# 03_DUT_ICs.net
KiCad netlist of a schematic drawn in Altium Designer
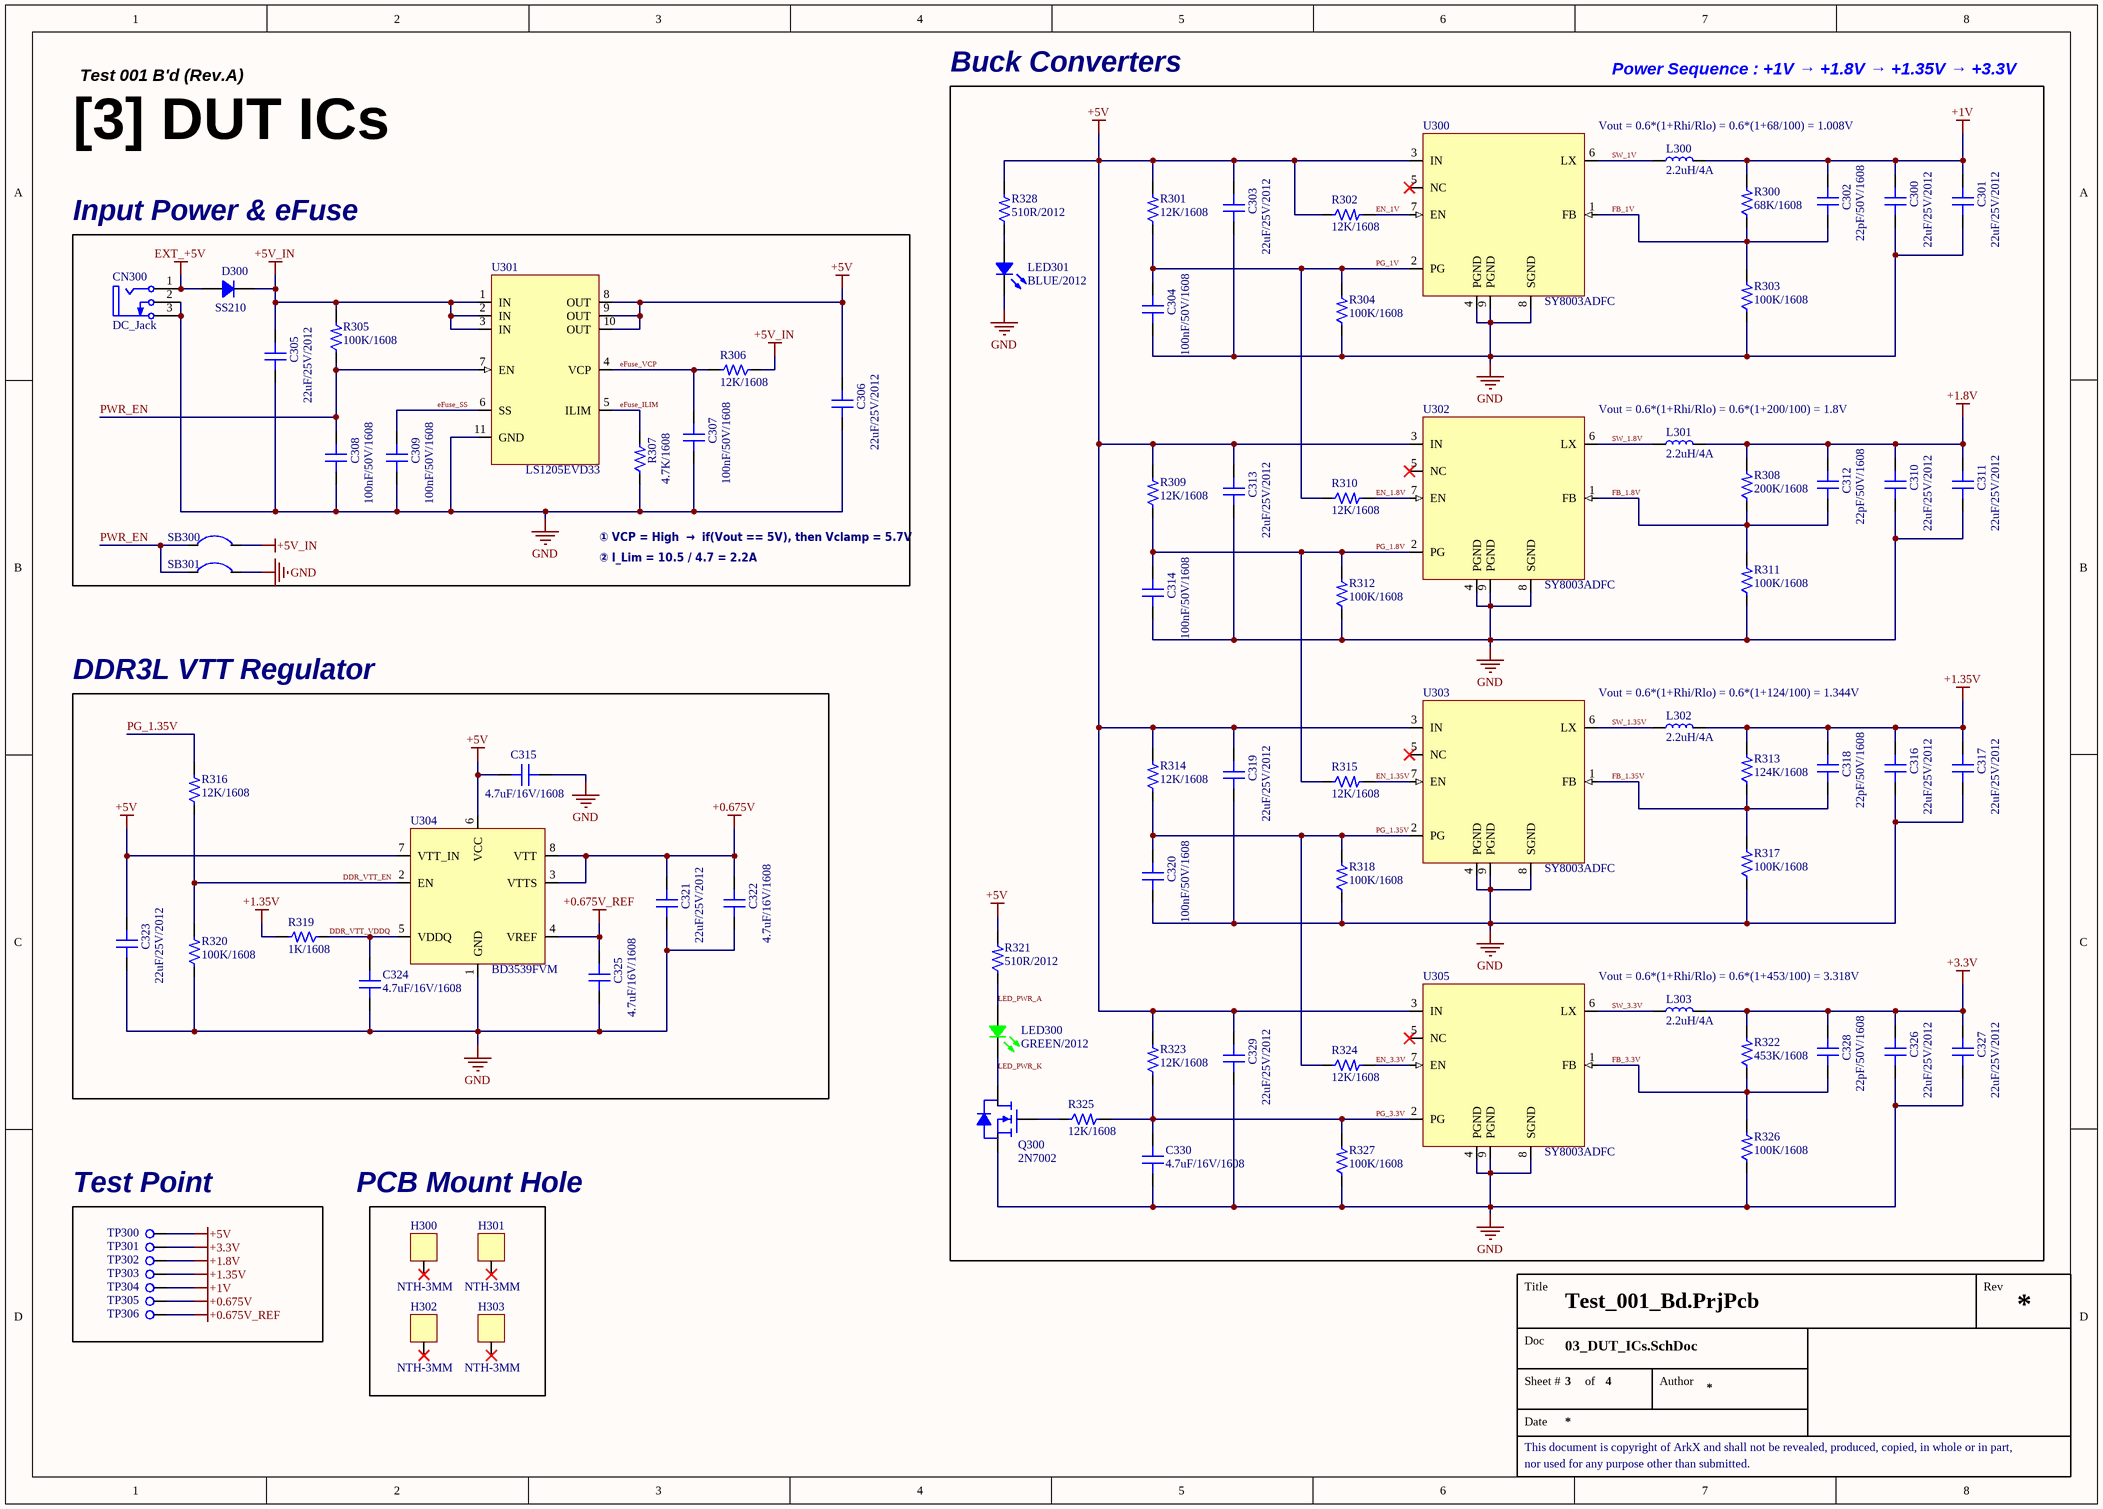
[diagram p0: 03_DUT_ICs.SchDoc]

(export (version "E")
  (design (tool "Eeschema 10.0.6"))
  (components
    (comp (ref "C300")
      (value "22uF/25V/2012")
      (footprint "CAP 2012 (0805_INCH)")
      (description "Ceramic CAP_22uF/25V/2012")
      (fields (field (name "LCSC PART #") "C45783"))
      (libsource (lib "Arkx") (part "CAP_22uF/25V/2012"))
    )
    (comp (ref "C301")
      (value "22uF/25V/2012")
      (footprint "CAP 2012 (0805_INCH)")
      (description "Ceramic CAP_22uF/25V/2012")
      (fields (field (name "LCSC PART #") "C45783"))
      (libsource (lib "Arkx") (part "CAP_22uF/25V/2012"))
    )
    (comp (ref "C302")
      (value "22pF/50V/1608")
      (footprint "CAP 1608 (0603_INCH)")
      (description "Ceramic CAP_22pF/50V/1608")
      (fields (field (name "LCSC PART #") "C1653"))
      (libsource (lib "Arkx") (part "CAP_22pF/50V/1608"))
    )
    (comp (ref "C303")
      (value "22uF/25V/2012")
      (footprint "CAP 2012 (0805_INCH)")
      (description "Ceramic CAP_22uF/25V/2012")
      (fields (field (name "LCSC PART #") "C45783"))
      (libsource (lib "Arkx") (part "CAP_22uF/25V/2012"))
    )
    (comp (ref "C304")
      (value "100nF/50V/1608")
      (footprint "CAP 1608 (0603_INCH)")
      (description "Ceramic CAP_100nF/50V/1608")
      (fields (field (name "LCSC PART #") "C14663"))
      (libsource (lib "Arkx") (part "CAP_100nF/50V/1608"))
    )
    (comp (ref "C305")
      (value "22uF/25V/2012")
      (footprint "CAP 2012 (0805_INCH)")
      (description "Ceramic CAP_22uF/25V/2012")
      (fields (field (name "LCSC PART #") "C45783"))
      (libsource (lib "Arkx") (part "CAP_22uF/25V/2012"))
    )
    (comp (ref "C306")
      (value "22uF/25V/2012")
      (footprint "CAP 2012 (0805_INCH)")
      (description "Ceramic CAP_22uF/25V/2012")
      (fields (field (name "LCSC PART #") "C45783"))
      (libsource (lib "Arkx") (part "CAP_22uF/25V/2012"))
    )
    (comp (ref "C307")
      (value "100nF/50V/1608")
      (footprint "CAP 1608 (0603_INCH)")
      (description "Ceramic CAP_100nF/50V/1608")
      (fields (field (name "LCSC PART #") "C14663"))
      (libsource (lib "Arkx") (part "CAP_100nF/50V/1608"))
    )
    (comp (ref "C308")
      (value "100nF/50V/1608")
      (footprint "CAP 1608 (0603_INCH)")
      (description "Ceramic CAP_100nF/50V/1608")
      (fields (field (name "LCSC PART #") "C14663"))
      (libsource (lib "Arkx") (part "CAP_100nF/50V/1608"))
    )
    (comp (ref "C309")
      (value "100nF/50V/1608")
      (footprint "CAP 1608 (0603_INCH)")
      (description "Ceramic CAP_100nF/50V/1608")
      (fields (field (name "LCSC PART #") "C14663"))
      (libsource (lib "Arkx") (part "CAP_100nF/50V/1608"))
    )
    (comp (ref "C310")
      (value "22uF/25V/2012")
      (footprint "CAP 2012 (0805_INCH)")
      (description "Ceramic CAP_22uF/25V/2012")
      (fields (field (name "LCSC PART #") "C45783"))
      (libsource (lib "Arkx") (part "CAP_22uF/25V/2012"))
    )
    (comp (ref "C311")
      (value "22uF/25V/2012")
      (footprint "CAP 2012 (0805_INCH)")
      (description "Ceramic CAP_22uF/25V/2012")
      (fields (field (name "LCSC PART #") "C45783"))
      (libsource (lib "Arkx") (part "CAP_22uF/25V/2012"))
    )
    (comp (ref "C312")
      (value "22pF/50V/1608")
      (footprint "CAP 1608 (0603_INCH)")
      (description "Ceramic CAP_22pF/50V/1608")
      (fields (field (name "LCSC PART #") "C1653"))
      (libsource (lib "Arkx") (part "CAP_22pF/50V/1608"))
    )
    (comp (ref "C313")
      (value "22uF/25V/2012")
      (footprint "CAP 2012 (0805_INCH)")
      (description "Ceramic CAP_22uF/25V/2012")
      (fields (field (name "LCSC PART #") "C45783"))
      (libsource (lib "Arkx") (part "CAP_22uF/25V/2012"))
    )
    (comp (ref "C314")
      (value "100nF/50V/1608")
      (footprint "CAP 1608 (0603_INCH)")
      (description "Ceramic CAP_100nF/50V/1608")
      (fields (field (name "LCSC PART #") "C14663"))
      (libsource (lib "Arkx") (part "CAP_100nF/50V/1608"))
    )
    (comp (ref "C315")
      (value "4.7uF/16V/1608")
      (footprint "CAP 1608 (0603_INCH)")
      (description "Ceramic CAP_4.7uF/16V/1608")
      (fields (field (name "LCSC PART #") "C19666"))
      (libsource (lib "Arkx") (part "CAP_4.7uF/16V/1608"))
    )
    (comp (ref "C316")
      (value "22uF/25V/2012")
      (footprint "CAP 2012 (0805_INCH)")
      (description "Ceramic CAP_22uF/25V/2012")
      (fields (field (name "LCSC PART #") "C45783"))
      (libsource (lib "Arkx") (part "CAP_22uF/25V/2012"))
    )
    (comp (ref "C317")
      (value "22uF/25V/2012")
      (footprint "CAP 2012 (0805_INCH)")
      (description "Ceramic CAP_22uF/25V/2012")
      (fields (field (name "LCSC PART #") "C45783"))
      (libsource (lib "Arkx") (part "CAP_22uF/25V/2012"))
    )
    (comp (ref "C318")
      (value "22pF/50V/1608")
      (footprint "CAP 1608 (0603_INCH)")
      (description "Ceramic CAP_22pF/50V/1608")
      (fields (field (name "LCSC PART #") "C1653"))
      (libsource (lib "Arkx") (part "CAP_22pF/50V/1608"))
    )
    (comp (ref "C319")
      (value "22uF/25V/2012")
      (footprint "CAP 2012 (0805_INCH)")
      (description "Ceramic CAP_22uF/25V/2012")
      (fields (field (name "LCSC PART #") "C45783"))
      (libsource (lib "Arkx") (part "CAP_22uF/25V/2012"))
    )
    (comp (ref "C320")
      (value "100nF/50V/1608")
      (footprint "CAP 1608 (0603_INCH)")
      (description "Ceramic CAP_100nF/50V/1608")
      (fields (field (name "LCSC PART #") "C14663"))
      (libsource (lib "Arkx") (part "CAP_100nF/50V/1608"))
    )
    (comp (ref "C321")
      (value "22uF/25V/2012")
      (footprint "CAP 2012 (0805_INCH)")
      (description "Ceramic CAP_22uF/25V/2012")
      (fields (field (name "LCSC PART #") "C45783"))
      (libsource (lib "Arkx") (part "CAP_22uF/25V/2012"))
    )
    (comp (ref "C322")
      (value "4.7uF/16V/1608")
      (footprint "CAP 1608 (0603_INCH)")
      (description "Ceramic CAP_4.7uF/16V/1608")
      (fields (field (name "LCSC PART #") "C19666"))
      (libsource (lib "Arkx") (part "CAP_4.7uF/16V/1608"))
    )
    (comp (ref "C323")
      (value "22uF/25V/2012")
      (footprint "CAP 2012 (0805_INCH)")
      (description "Ceramic CAP_22uF/25V/2012")
      (fields (field (name "LCSC PART #") "C45783"))
      (libsource (lib "Arkx") (part "CAP_22uF/25V/2012"))
    )
    (comp (ref "C324")
      (value "4.7uF/16V/1608")
      (footprint "CAP 1608 (0603_INCH)")
      (description "Ceramic CAP_4.7uF/16V/1608")
      (fields (field (name "LCSC PART #") "C19666"))
      (libsource (lib "Arkx") (part "CAP_4.7uF/16V/1608"))
    )
    (comp (ref "C325")
      (value "4.7uF/16V/1608")
      (footprint "CAP 1608 (0603_INCH)")
      (description "Ceramic CAP_4.7uF/16V/1608")
      (fields (field (name "LCSC PART #") "C19666"))
      (libsource (lib "Arkx") (part "CAP_4.7uF/16V/1608"))
    )
    (comp (ref "C326")
      (value "22uF/25V/2012")
      (footprint "CAP 2012 (0805_INCH)")
      (description "Ceramic CAP_22uF/25V/2012")
      (fields (field (name "LCSC PART #") "C45783"))
      (libsource (lib "Arkx") (part "CAP_22uF/25V/2012"))
    )
    (comp (ref "C327")
      (value "22uF/25V/2012")
      (footprint "CAP 2012 (0805_INCH)")
      (description "Ceramic CAP_22uF/25V/2012")
      (fields (field (name "LCSC PART #") "C45783"))
      (libsource (lib "Arkx") (part "CAP_22uF/25V/2012"))
    )
    (comp (ref "C328")
      (value "22pF/50V/1608")
      (footprint "CAP 1608 (0603_INCH)")
      (description "Ceramic CAP_22pF/50V/1608")
      (fields (field (name "LCSC PART #") "C1653"))
      (libsource (lib "Arkx") (part "CAP_22pF/50V/1608"))
    )
    (comp (ref "C329")
      (value "22uF/25V/2012")
      (footprint "CAP 2012 (0805_INCH)")
      (description "Ceramic CAP_22uF/25V/2012")
      (fields (field (name "LCSC PART #") "C45783"))
      (libsource (lib "Arkx") (part "CAP_22uF/25V/2012"))
    )
    (comp (ref "C330")
      (value "4.7uF/16V/1608")
      (footprint "CAP 1608 (0603_INCH)")
      (description "Ceramic CAP_4.7uF/16V/1608")
      (fields (field (name "LCSC PART #") "C19666"))
      (libsource (lib "Arkx") (part "CAP_4.7uF/16V/1608"))
    )
    (comp (ref "CN300")
      (value "DC_Jack")
      (footprint "CON DC-Jack")
      (libsource (lib "Arkx") (part "CON_DC-Jack"))
    )
    (comp (ref "D300")
      (value "SS210")
      (footprint "DIO DO-214AC (SMA)")
      (description "100V 850mV@2A 2A SMA(DO-214AC)  Schottky Barrier Diodes (SBD) ROHS")
      (fields (field (name "LCSC PART #") "C14996"))
      (libsource (lib "Arkx") (part "DIO_SS210"))
    )
    (comp (ref "H300")
      (value "NTH-3MM")
      (footprint "HOLE NTH-3MM")
      (description "Non-Through Hole 3mm")
      (libsource (lib "Arkx") (part "HOLE_NTH-3MM"))
    )
    (comp (ref "H301")
      (value "NTH-3MM")
      (footprint "HOLE NTH-3MM")
      (description "Non-Through Hole 3mm")
      (libsource (lib "Arkx") (part "HOLE_NTH-3MM"))
    )
    (comp (ref "H302")
      (value "NTH-3MM")
      (footprint "HOLE NTH-3MM")
      (description "Non-Through Hole 3mm")
      (libsource (lib "Arkx") (part "HOLE_NTH-3MM"))
    )
    (comp (ref "H303")
      (value "NTH-3MM")
      (footprint "HOLE NTH-3MM")
      (description "Non-Through Hole 3mm")
      (libsource (lib "Arkx") (part "HOLE_NTH-3MM"))
    )
    (comp (ref "L300")
      (value "2.2uH/4A")
      (footprint "IND BWVS006060282R2M00")
      (description "FIXED IND 2.2uH 4A 20mohm SMD")
      (libsource (lib "Arkx") (part "IND_BWVS006060282R2M00"))
    )
    (comp (ref "L301")
      (value "2.2uH/4A")
      (footprint "IND BWVS006060282R2M00")
      (description "FIXED IND 2.2uH 4A 20mohm SMD")
      (libsource (lib "Arkx") (part "IND_BWVS006060282R2M00"))
    )
    (comp (ref "L302")
      (value "2.2uH/4A")
      (footprint "IND BWVS006060282R2M00")
      (description "FIXED IND 2.2uH 4A 20mohm SMD")
      (libsource (lib "Arkx") (part "IND_BWVS006060282R2M00"))
    )
    (comp (ref "L303")
      (value "2.2uH/4A")
      (footprint "IND BWVS006060282R2M00")
      (description "FIXED IND 2.2uH 4A 20mohm SMD")
      (libsource (lib "Arkx") (part "IND_BWVS006060282R2M00"))
    )
    (comp (ref "LED300")
      (value "GREEN/2012")
      (footprint "LED MHT170RGBCT (GREEN)")
      (fields (field (name "LCSC PART #") "C2962094"))
      (libsource (lib "Arkx") (part "LED_MHT170RGBCT(GREEN)"))
    )
    (comp (ref "LED301")
      (value "BLUE/2012")
      (footprint "LED MHT170RGBCT (BLUE)")
      (fields (field (name "LCSC PART #") "C2962094"))
      (libsource (lib "Arkx") (part "LED_MHT170RGBCT(BLUE)"))
    )
    (comp (ref "Q300")
      (value "2N7002")
      (footprint "SOT 23-3 (DIODES INCORPORATED)")
      (description "60V 115mA 200mW 7.5Ω@10V,500mA N Channel SOT-23  MOSFETs ROHS")
      (fields (field (name "LCSC PART #") "C8545"))
      (libsource (lib "Arkx") (part "FET_2N7002"))
    )
    (comp (ref "R300")
      (value "68K/1608")
      (footprint "RES 1608 (0603_inch)")
      (description "RES_68K/1608/0.1W")
      (fields (field (name "LCSC PART #") "C23231"))
      (libsource (lib "Arkx") (part "RES_68K/1608/0.1W"))
    )
    (comp (ref "R301")
      (value "12K/1608")
      (footprint "RES 1608 (0603_inch)")
      (description "RES_12K/1608/0.1W")
      (fields (field (name "LCSC PART #") "C22790"))
      (libsource (lib "Arkx") (part "RES_12K/1608/0.1W"))
    )
    (comp (ref "R302")
      (value "12K/1608")
      (footprint "RES 1608 (0603_inch)")
      (description "RES_12K/1608/0.1W")
      (fields (field (name "LCSC PART #") "C22790"))
      (libsource (lib "Arkx") (part "RES_12K/1608/0.1W"))
    )
    (comp (ref "R303")
      (value "100K/1608")
      (footprint "RES 1608 (0603_inch)")
      (description "RES_100K/1608/0.1W")
      (fields (field (name "LCSC PART #") "C25803"))
      (libsource (lib "Arkx") (part "RES_100K/1608/0.1W"))
    )
    (comp (ref "R304")
      (value "100K/1608")
      (footprint "RES 1608 (0603_inch)")
      (description "RES_100K/1608/0.1W")
      (fields (field (name "LCSC PART #") "C25803"))
      (libsource (lib "Arkx") (part "RES_100K/1608/0.1W"))
    )
    (comp (ref "R305")
      (value "100K/1608")
      (footprint "RES 1608 (0603_inch)")
      (description "RES_100K/1608/0.1W")
      (fields (field (name "LCSC PART #") "C25803"))
      (libsource (lib "Arkx") (part "RES_100K/1608/0.1W"))
    )
    (comp (ref "R306")
      (value "12K/1608")
      (footprint "RES 1608 (0603_inch)")
      (description "RES_12K/1608/0.1W")
      (fields (field (name "LCSC PART #") "C22790"))
      (libsource (lib "Arkx") (part "RES_12K/1608/0.1W"))
    )
    (comp (ref "R307")
      (value "4.7K/1608")
      (footprint "RES 1608 (0603_inch)")
      (description "RES_4.7K/1608/0.1W")
      (fields (field (name "LCSC PART #") "C23162"))
      (libsource (lib "Arkx") (part "RES_4.7K/1608/0.1W"))
    )
    (comp (ref "R308")
      (value "200K/1608")
      (footprint "RES 1608 (0603_inch)")
      (description "RES_200K/1608/0.1W")
      (fields (field (name "LCSC PART #") "C25811"))
      (libsource (lib "Arkx") (part "RES_200K/1608/0.1W"))
    )
    (comp (ref "R309")
      (value "12K/1608")
      (footprint "RES 1608 (0603_inch)")
      (description "RES_12K/1608/0.1W")
      (fields (field (name "LCSC PART #") "C22790"))
      (libsource (lib "Arkx") (part "RES_12K/1608/0.1W"))
    )
    (comp (ref "R310")
      (value "12K/1608")
      (footprint "RES 1608 (0603_inch)")
      (description "RES_12K/1608/0.1W")
      (fields (field (name "LCSC PART #") "C22790"))
      (libsource (lib "Arkx") (part "RES_12K/1608/0.1W"))
    )
    (comp (ref "R311")
      (value "100K/1608")
      (footprint "RES 1608 (0603_inch)")
      (description "RES_100K/1608/0.1W")
      (fields (field (name "LCSC PART #") "C25803"))
      (libsource (lib "Arkx") (part "RES_100K/1608/0.1W"))
    )
    (comp (ref "R312")
      (value "100K/1608")
      (footprint "RES 1608 (0603_inch)")
      (description "RES_100K/1608/0.1W")
      (fields (field (name "LCSC PART #") "C25803"))
      (libsource (lib "Arkx") (part "RES_100K/1608/0.1W"))
    )
    (comp (ref "R313")
      (value "124K/1608")
      (footprint "RES 1608 (0603_inch)")
      (description "RES_124K/1608/0.1W")
      (fields (field (name "LCSC PART #") "C140118"))
      (libsource (lib "Arkx") (part "RES_124K/1608/0.1W"))
    )
    (comp (ref "R314")
      (value "12K/1608")
      (footprint "RES 1608 (0603_inch)")
      (description "RES_12K/1608/0.1W")
      (fields (field (name "LCSC PART #") "C22790"))
      (libsource (lib "Arkx") (part "RES_12K/1608/0.1W"))
    )
    (comp (ref "R315")
      (value "12K/1608")
      (footprint "RES 1608 (0603_inch)")
      (description "RES_12K/1608/0.1W")
      (fields (field (name "LCSC PART #") "C22790"))
      (libsource (lib "Arkx") (part "RES_12K/1608/0.1W"))
    )
    (comp (ref "R316")
      (value "12K/1608")
      (footprint "RES 1608 (0603_inch)")
      (description "RES_12K/1608/0.1W")
      (fields (field (name "LCSC PART #") "C22790"))
      (libsource (lib "Arkx") (part "RES_12K/1608/0.1W"))
    )
    (comp (ref "R317")
      (value "100K/1608")
      (footprint "RES 1608 (0603_inch)")
      (description "RES_100K/1608/0.1W")
      (fields (field (name "LCSC PART #") "C25803"))
      (libsource (lib "Arkx") (part "RES_100K/1608/0.1W"))
    )
    (comp (ref "R318")
      (value "100K/1608")
      (footprint "RES 1608 (0603_inch)")
      (description "RES_100K/1608/0.1W")
      (fields (field (name "LCSC PART #") "C25803"))
      (libsource (lib "Arkx") (part "RES_100K/1608/0.1W"))
    )
    (comp (ref "R319")
      (value "1K/1608")
      (footprint "RES 1608 (0603_inch)")
      (description "RES_1K/1608/0.1W")
      (fields (field (name "LCSC PART #") "C21190"))
      (libsource (lib "Arkx") (part "RES_1K/1608/0.1W"))
    )
    (comp (ref "R320")
      (value "100K/1608")
      (footprint "RES 1608 (0603_inch)")
      (description "RES_100K/1608/0.1W")
      (fields (field (name "LCSC PART #") "C25803"))
      (libsource (lib "Arkx") (part "RES_100K/1608/0.1W"))
    )
    (comp (ref "R321")
      (value "510R/2012")
      (footprint "RES 2012 (0805_inch)")
      (description "RES_510R/2012/0.125W")
      (fields (field (name "LCSC PART #") "C17734"))
      (libsource (lib "Arkx") (part "RES_510R/2012/0.125W"))
    )
    (comp (ref "R322")
      (value "453K/1608")
      (footprint "RES 1608 (0603_inch)")
      (description "RES_453K/1608/0.1W")
      (fields (field (name "LCSC PART #") "C25818"))
      (libsource (lib "Arkx") (part "RES_453K/1608/0.1W"))
    )
    (comp (ref "R323")
      (value "12K/1608")
      (footprint "RES 1608 (0603_inch)")
      (description "RES_12K/1608/0.1W")
      (fields (field (name "LCSC PART #") "C22790"))
      (libsource (lib "Arkx") (part "RES_12K/1608/0.1W"))
    )
    (comp (ref "R324")
      (value "12K/1608")
      (footprint "RES 1608 (0603_inch)")
      (description "RES_12K/1608/0.1W")
      (fields (field (name "LCSC PART #") "C22790"))
      (libsource (lib "Arkx") (part "RES_12K/1608/0.1W"))
    )
    (comp (ref "R325")
      (value "12K/1608")
      (footprint "RES 1608 (0603_inch)")
      (description "RES_12K/1608/0.1W")
      (fields (field (name "LCSC PART #") "C22790"))
      (libsource (lib "Arkx") (part "RES_12K/1608/0.1W"))
    )
    (comp (ref "R326")
      (value "100K/1608")
      (footprint "RES 1608 (0603_inch)")
      (description "RES_100K/1608/0.1W")
      (fields (field (name "LCSC PART #") "C25803"))
      (libsource (lib "Arkx") (part "RES_100K/1608/0.1W"))
    )
    (comp (ref "R327")
      (value "100K/1608")
      (footprint "RES 1608 (0603_inch)")
      (description "RES_100K/1608/0.1W")
      (fields (field (name "LCSC PART #") "C25803"))
      (libsource (lib "Arkx") (part "RES_100K/1608/0.1W"))
    )
    (comp (ref "R328")
      (value "510R/2012")
      (footprint "RES 2012 (0805_inch)")
      (description "RES_510R/2012/0.125W")
      (fields (field (name "LCSC PART #") "C17734"))
      (libsource (lib "Arkx") (part "RES_510R/2012/0.125W"))
    )
    (comp (ref "SB300")
      (value "SB")
      (footprint "SB (Solder-Bridge)")
      (description "SB_Solder-Bridge")
      (libsource (lib "Arkx") (part "SB_Solder-Bridge"))
    )
    (comp (ref "SB301")
      (value "SB")
      (footprint "SB (Solder-Bridge)")
      (description "SB_Solder-Bridge")
      (libsource (lib "Arkx") (part "SB_Solder-Bridge"))
    )
    (comp (ref "TP300")
      (value "TP_CIRCLE")
      (footprint "TP Circle")
      (libsource (lib "Arkx") (part "TP_CIRCLE"))
    )
    (comp (ref "TP301")
      (value "TP_CIRCLE")
      (footprint "TP Circle")
      (libsource (lib "Arkx") (part "TP_CIRCLE"))
    )
    (comp (ref "TP302")
      (value "TP_CIRCLE")
      (footprint "TP Circle")
      (libsource (lib "Arkx") (part "TP_CIRCLE"))
    )
    (comp (ref "TP303")
      (value "TP_CIRCLE")
      (footprint "TP Circle")
      (libsource (lib "Arkx") (part "TP_CIRCLE"))
    )
    (comp (ref "TP304")
      (value "TP_CIRCLE")
      (footprint "TP Circle")
      (libsource (lib "Arkx") (part "TP_CIRCLE"))
    )
    (comp (ref "TP305")
      (value "TP_CIRCLE")
      (footprint "TP Circle")
      (libsource (lib "Arkx") (part "TP_CIRCLE"))
    )
    (comp (ref "TP306")
      (value "TP_CIRCLE")
      (footprint "TP Circle")
      (libsource (lib "Arkx") (part "TP_CIRCLE"))
    )
    (comp (ref "U300")
      (value "SY8003ADFC")
      (footprint "IC_DFN_2X2_8L")
      (description "High Efficiency 5.5V, 3A Continuous, 1MHz Synchronous Step Down Regulator")
      (fields
        (field (name "MANUFACTURER") "Silergy")
        (field (name "MANUFACTURER PART NUMBER") "High Efficiency 5.5V, 3A continuous, 1MHz")
      )
      (libsource (lib "Arkx") (part "IC_REG_SY8003ADFC"))
    )
    (comp (ref "U301")
      (value "LS1205EVD33")
      (footprint "IC_DFN_3x3_10L")
      (description "18V, 5A eFuse with Programmable Current Limit and Output Voltage Clamp, 10-DFN (3x3)")
      (libsource (lib "Arkx") (part "IC_eFUSE_LS1205EVD33"))
    )
    (comp (ref "U302")
      (value "SY8003ADFC")
      (footprint "IC_DFN_2X2_8L")
      (description "High Efficiency 5.5V, 3A Continuous, 1MHz Synchronous Step Down Regulator")
      (fields
        (field (name "MANUFACTURER") "Silergy")
        (field (name "MANUFACTURER PART NUMBER") "High Efficiency 5.5V, 3A continuous, 1MHz")
      )
      (libsource (lib "Arkx") (part "IC_REG_SY8003ADFC"))
    )
    (comp (ref "U303")
      (value "SY8003ADFC")
      (footprint "IC_DFN_2X2_8L")
      (description "High Efficiency 5.5V, 3A Continuous, 1MHz Synchronous Step Down Regulator")
      (fields
        (field (name "MANUFACTURER") "Silergy")
        (field (name "MANUFACTURER PART NUMBER") "High Efficiency 5.5V, 3A continuous, 1MHz")
      )
      (libsource (lib "Arkx") (part "IC_REG_SY8003ADFC"))
    )
    (comp (ref "U304")
      (value "BD3539FVM")
      (footprint "IC_MSOP-8")
      (description "1.0V to 5.5V, 1A 1ch\r\nTermination Regulators for DDR-SDRAMs, 8-MSOP")
      (libsource (lib "Arkx") (part "IC_REG_VTT_BD3539FVM"))
    )
    (comp (ref "U305")
      (value "SY8003ADFC")
      (footprint "IC_DFN_2X2_8L")
      (description "High Efficiency 5.5V, 3A Continuous, 1MHz Synchronous Step Down Regulator")
      (fields
        (field (name "MANUFACTURER") "Silergy")
        (field (name "MANUFACTURER PART NUMBER") "High Efficiency 5.5V, 3A continuous, 1MHz")
      )
      (libsource (lib "Arkx") (part "IC_REG_SY8003ADFC"))
    )
  )
  (nets
    (net (code "1") (name "+0.675V") (class "Default")
      (node (ref "C321") (pin "2") (pinfunction "2_2") (pintype "passive"))
      (node (ref "C322") (pin "2") (pinfunction "2_2") (pintype "passive"))
      (node (ref "TP305") (pin "1") (pinfunction "TP_1") (pintype "passive"))
      (node (ref "U304") (pin "3") (pinfunction "VTTS_3") (pintype "passive"))
      (node (ref "U304") (pin "8") (pinfunction "VTT_8") (pintype "passive"))
    )
    (net (code "2") (name "+0.675V_REF") (class "Default")
      (node (ref "C325") (pin "2") (pinfunction "2_2") (pintype "passive"))
      (node (ref "TP306") (pin "1") (pinfunction "TP_1") (pintype "passive"))
      (node (ref "U304") (pin "4") (pinfunction "VREF_4") (pintype "passive"))
    )
    (net (code "3") (name "+1.8V") (class "Default")
      (node (ref "C310") (pin "2") (pinfunction "2_2") (pintype "passive"))
      (node (ref "C311") (pin "2") (pinfunction "2_2") (pintype "passive"))
      (node (ref "C312") (pin "2") (pinfunction "2_2") (pintype "passive"))
      (node (ref "L301") (pin "2") (pinfunction "2_2") (pintype "passive"))
      (node (ref "R308") (pin "2") (pinfunction "2_2") (pintype "passive"))
      (node (ref "TP302") (pin "1") (pinfunction "TP_1") (pintype "passive"))
    )
    (net (code "4") (name "+1.35V") (class "Default")
      (node (ref "C316") (pin "2") (pinfunction "2_2") (pintype "passive"))
      (node (ref "C317") (pin "2") (pinfunction "2_2") (pintype "passive"))
      (node (ref "C318") (pin "2") (pinfunction "2_2") (pintype "passive"))
      (node (ref "L302") (pin "2") (pinfunction "2_2") (pintype "passive"))
      (node (ref "R313") (pin "2") (pinfunction "2_2") (pintype "passive"))
      (node (ref "R319") (pin "2") (pinfunction "2_2") (pintype "passive"))
      (node (ref "TP303") (pin "1") (pinfunction "TP_1") (pintype "passive"))
    )
    (net (code "5") (name "+1V") (class "Default")
      (node (ref "C300") (pin "2") (pinfunction "2_2") (pintype "passive"))
      (node (ref "C301") (pin "2") (pinfunction "2_2") (pintype "passive"))
      (node (ref "C302") (pin "2") (pinfunction "2_2") (pintype "passive"))
      (node (ref "L300") (pin "2") (pinfunction "2_2") (pintype "passive"))
      (node (ref "R300") (pin "2") (pinfunction "2_2") (pintype "passive"))
      (node (ref "TP304") (pin "1") (pinfunction "TP_1") (pintype "passive"))
    )
    (net (code "6") (name "+3.3V") (class "Default")
      (node (ref "C326") (pin "2") (pinfunction "2_2") (pintype "passive"))
      (node (ref "C327") (pin "2") (pinfunction "2_2") (pintype "passive"))
      (node (ref "C328") (pin "2") (pinfunction "2_2") (pintype "passive"))
      (node (ref "L303") (pin "2") (pinfunction "2_2") (pintype "passive"))
      (node (ref "R322") (pin "2") (pinfunction "2_2") (pintype "passive"))
      (node (ref "TP301") (pin "1") (pinfunction "TP_1") (pintype "passive"))
    )
    (net (code "7") (name "+5V") (class "Default")
      (node (ref "C303") (pin "2") (pinfunction "2_2") (pintype "passive"))
      (node (ref "C306") (pin "2") (pinfunction "2_2") (pintype "passive"))
      (node (ref "C313") (pin "2") (pinfunction "2_2") (pintype "passive"))
      (node (ref "C315") (pin "2") (pinfunction "2_2") (pintype "passive"))
      (node (ref "C319") (pin "2") (pinfunction "2_2") (pintype "passive"))
      (node (ref "C323") (pin "2") (pinfunction "2_2") (pintype "passive"))
      (node (ref "C329") (pin "2") (pinfunction "2_2") (pintype "passive"))
      (node (ref "R301") (pin "2") (pinfunction "2_2") (pintype "passive"))
      (node (ref "R302") (pin "1") (pinfunction "1_1") (pintype "passive"))
      (node (ref "R309") (pin "2") (pinfunction "2_2") (pintype "passive"))
      (node (ref "R314") (pin "2") (pinfunction "2_2") (pintype "passive"))
      (node (ref "R321") (pin "2") (pinfunction "2_2") (pintype "passive"))
      (node (ref "R323") (pin "2") (pinfunction "2_2") (pintype "passive"))
      (node (ref "R328") (pin "2") (pinfunction "2_2") (pintype "passive"))
      (node (ref "TP300") (pin "1") (pinfunction "TP_1") (pintype "passive"))
      (node (ref "U300") (pin "3") (pinfunction "IN_3") (pintype "power_in"))
      (node (ref "U301") (pin "10") (pinfunction "OUT_10") (pintype "power_in"))
      (node (ref "U301") (pin "8") (pinfunction "OUT_8") (pintype "power_in"))
      (node (ref "U301") (pin "9") (pinfunction "OUT_9") (pintype "power_in"))
      (node (ref "U302") (pin "3") (pinfunction "IN_3") (pintype "power_in"))
      (node (ref "U303") (pin "3") (pinfunction "IN_3") (pintype "power_in"))
      (node (ref "U304") (pin "6") (pinfunction "VCC_6") (pintype "passive"))
      (node (ref "U304") (pin "7") (pinfunction "VTT_IN_7") (pintype "passive"))
      (node (ref "U305") (pin "3") (pinfunction "IN_3") (pintype "power_in"))
    )
    (net (code "8") (name "+5V_IN") (class "Default")
      (node (ref "C305") (pin "2") (pinfunction "2_2") (pintype "passive"))
      (node (ref "D300") (pin "2") (pinfunction "2_2") (pintype "passive"))
      (node (ref "R305") (pin "2") (pinfunction "2_2") (pintype "passive"))
      (node (ref "R306") (pin "1") (pinfunction "1_1") (pintype "passive"))
      (node (ref "SB300") (pin "2") (pinfunction "2_2") (pintype "passive"))
      (node (ref "U301") (pin "1") (pinfunction "IN_1") (pintype "power_in"))
      (node (ref "U301") (pin "2") (pinfunction "IN_2") (pintype "power_in"))
      (node (ref "U301") (pin "3") (pinfunction "IN_3") (pintype "power_in"))
    )
    (net (code "9") (name "/DDR_VTT_EN") (class "Default")
      (node (ref "R316") (pin "1") (pinfunction "1_1") (pintype "passive"))
      (node (ref "R320") (pin "2") (pinfunction "2_2") (pintype "passive"))
      (node (ref "U304") (pin "2") (pinfunction "EN_2") (pintype "passive"))
    )
    (net (code "10") (name "/DDR_VTT_VDDQ") (class "Default")
      (node (ref "C324") (pin "2") (pinfunction "2_2") (pintype "passive"))
      (node (ref "R319") (pin "1") (pinfunction "1_1") (pintype "passive"))
      (node (ref "U304") (pin "5") (pinfunction "VDDQ_5") (pintype "passive"))
    )
    (net (code "11") (name "/EN_1.8V") (class "Default")
      (node (ref "R310") (pin "2") (pinfunction "2_2") (pintype "passive"))
      (node (ref "U302") (pin "7") (pinfunction "EN_7") (pintype "input"))
    )
    (net (code "12") (name "/EN_1.35V") (class "Default")
      (node (ref "R315") (pin "2") (pinfunction "2_2") (pintype "passive"))
      (node (ref "U303") (pin "7") (pinfunction "EN_7") (pintype "input"))
    )
    (net (code "13") (name "/EN_1V") (class "Default")
      (node (ref "R302") (pin "2") (pinfunction "2_2") (pintype "passive"))
      (node (ref "U300") (pin "7") (pinfunction "EN_7") (pintype "input"))
    )
    (net (code "14") (name "/EN_3.3V") (class "Default")
      (node (ref "R324") (pin "2") (pinfunction "2_2") (pintype "passive"))
      (node (ref "U305") (pin "7") (pinfunction "EN_7") (pintype "input"))
    )
    (net (code "15") (name "/FB_1.8V") (class "Default")
      (node (ref "C312") (pin "1") (pinfunction "1_1") (pintype "passive"))
      (node (ref "R308") (pin "1") (pinfunction "1_1") (pintype "passive"))
      (node (ref "R311") (pin "2") (pinfunction "2_2") (pintype "passive"))
      (node (ref "U302") (pin "1") (pinfunction "FB_1") (pintype "input"))
    )
    (net (code "16") (name "/FB_1.35V") (class "Default")
      (node (ref "C318") (pin "1") (pinfunction "1_1") (pintype "passive"))
      (node (ref "R313") (pin "1") (pinfunction "1_1") (pintype "passive"))
      (node (ref "R317") (pin "2") (pinfunction "2_2") (pintype "passive"))
      (node (ref "U303") (pin "1") (pinfunction "FB_1") (pintype "input"))
    )
    (net (code "17") (name "/FB_1V") (class "Default")
      (node (ref "C302") (pin "1") (pinfunction "1_1") (pintype "passive"))
      (node (ref "R300") (pin "1") (pinfunction "1_1") (pintype "passive"))
      (node (ref "R303") (pin "2") (pinfunction "2_2") (pintype "passive"))
      (node (ref "U300") (pin "1") (pinfunction "FB_1") (pintype "input"))
    )
    (net (code "18") (name "/FB_3.3V") (class "Default")
      (node (ref "C328") (pin "1") (pinfunction "1_1") (pintype "passive"))
      (node (ref "R322") (pin "1") (pinfunction "1_1") (pintype "passive"))
      (node (ref "R326") (pin "2") (pinfunction "2_2") (pintype "passive"))
      (node (ref "U305") (pin "1") (pinfunction "FB_1") (pintype "input"))
    )
    (net (code "19") (name "/LED_PWR_A") (class "Default")
      (node (ref "LED300") (pin "4") (pinfunction "Common_Anode_4") (pintype "passive"))
      (node (ref "R321") (pin "1") (pinfunction "1_1") (pintype "passive"))
    )
    (net (code "20") (name "/LED_PWR_K") (class "Default")
      (node (ref "LED300") (pin "2") (pinfunction "GREEN_2") (pintype "passive"))
      (node (ref "Q300") (pin "3") (pinfunction "D_3") (pintype "passive"))
    )
    (net (code "21") (name "/PG_1.8V") (class "Default")
      (node (ref "C314") (pin "2") (pinfunction "2_2") (pintype "passive"))
      (node (ref "R309") (pin "1") (pinfunction "1_1") (pintype "passive"))
      (node (ref "R312") (pin "2") (pinfunction "2_2") (pintype "passive"))
      (node (ref "R315") (pin "1") (pinfunction "1_1") (pintype "passive"))
      (node (ref "U302") (pin "2") (pinfunction "PG_2") (pintype "open_collector"))
    )
    (net (code "22") (name "/PG_1.35V") (class "Default")
      (node (ref "C320") (pin "2") (pinfunction "2_2") (pintype "passive"))
      (node (ref "R314") (pin "1") (pinfunction "1_1") (pintype "passive"))
      (node (ref "R316") (pin "2") (pinfunction "2_2") (pintype "passive"))
      (node (ref "R318") (pin "2") (pinfunction "2_2") (pintype "passive"))
      (node (ref "R324") (pin "1") (pinfunction "1_1") (pintype "passive"))
      (node (ref "U303") (pin "2") (pinfunction "PG_2") (pintype "open_collector"))
    )
    (net (code "23") (name "/PG_1V") (class "Default")
      (node (ref "C304") (pin "2") (pinfunction "2_2") (pintype "passive"))
      (node (ref "R301") (pin "1") (pinfunction "1_1") (pintype "passive"))
      (node (ref "R304") (pin "2") (pinfunction "2_2") (pintype "passive"))
      (node (ref "R310") (pin "1") (pinfunction "1_1") (pintype "passive"))
      (node (ref "U300") (pin "2") (pinfunction "PG_2") (pintype "open_collector"))
    )
    (net (code "24") (name "/PG_3.3V") (class "Default")
      (node (ref "C330") (pin "2") (pinfunction "2_2") (pintype "passive"))
      (node (ref "R323") (pin "1") (pinfunction "1_1") (pintype "passive"))
      (node (ref "R325") (pin "2") (pinfunction "2_2") (pintype "passive"))
      (node (ref "R327") (pin "2") (pinfunction "2_2") (pintype "passive"))
      (node (ref "U305") (pin "2") (pinfunction "PG_2") (pintype "open_collector"))
    )
    (net (code "25") (name "/PWR_EN") (class "Default")
      (node (ref "C308") (pin "2") (pinfunction "2_2") (pintype "passive"))
      (node (ref "R305") (pin "1") (pinfunction "1_1") (pintype "passive"))
      (node (ref "SB300") (pin "1") (pinfunction "1_1") (pintype "passive"))
      (node (ref "SB301") (pin "1") (pinfunction "1_1") (pintype "passive"))
      (node (ref "U301") (pin "7") (pinfunction "EN_7") (pintype "input"))
    )
    (net (code "26") (name "/SW_1.8V") (class "Default")
      (node (ref "L301") (pin "1") (pinfunction "1_1") (pintype "passive"))
      (node (ref "U302") (pin "6") (pinfunction "LX_6") (pintype "power_in"))
    )
    (net (code "27") (name "/SW_1.35V") (class "Default")
      (node (ref "L302") (pin "1") (pinfunction "1_1") (pintype "passive"))
      (node (ref "U303") (pin "6") (pinfunction "LX_6") (pintype "power_in"))
    )
    (net (code "28") (name "/SW_1V") (class "Default")
      (node (ref "L300") (pin "1") (pinfunction "1_1") (pintype "passive"))
      (node (ref "U300") (pin "6") (pinfunction "LX_6") (pintype "power_in"))
    )
    (net (code "29") (name "/SW_3.3V") (class "Default")
      (node (ref "L303") (pin "1") (pinfunction "1_1") (pintype "passive"))
      (node (ref "U305") (pin "6") (pinfunction "LX_6") (pintype "power_in"))
    )
    (net (code "30") (name "/eFuse_ILIM") (class "Default")
      (node (ref "R307") (pin "2") (pinfunction "2_2") (pintype "passive"))
      (node (ref "U301") (pin "5") (pinfunction "ILIM_5") (pintype "passive"))
    )
    (net (code "31") (name "/eFuse_SS") (class "Default")
      (node (ref "C309") (pin "2") (pinfunction "2_2") (pintype "passive"))
      (node (ref "U301") (pin "6") (pinfunction "SS_6") (pintype "passive"))
    )
    (net (code "32") (name "/eFuse_VCP") (class "Default")
      (node (ref "C307") (pin "2") (pinfunction "2_2") (pintype "passive"))
      (node (ref "R306") (pin "2") (pinfunction "2_2") (pintype "passive"))
      (node (ref "U301") (pin "4") (pinfunction "VCP_4") (pintype "passive"))
    )
    (net (code "33") (name "EXT_+5V") (class "Default")
      (node (ref "CN300") (pin "1") (pinfunction "VCC_1") (pintype "power_in"))
      (node (ref "D300") (pin "1") (pinfunction "1_1") (pintype "passive"))
    )
    (net (code "34") (name "GND") (class "Default")
      (node (ref "C300") (pin "1") (pinfunction "1_1") (pintype "passive"))
      (node (ref "C301") (pin "1") (pinfunction "1_1") (pintype "passive"))
      (node (ref "C303") (pin "1") (pinfunction "1_1") (pintype "passive"))
      (node (ref "C304") (pin "1") (pinfunction "1_1") (pintype "passive"))
      (node (ref "C305") (pin "1") (pinfunction "1_1") (pintype "passive"))
      (node (ref "C306") (pin "1") (pinfunction "1_1") (pintype "passive"))
      (node (ref "C307") (pin "1") (pinfunction "1_1") (pintype "passive"))
      (node (ref "C308") (pin "1") (pinfunction "1_1") (pintype "passive"))
      (node (ref "C309") (pin "1") (pinfunction "1_1") (pintype "passive"))
      (node (ref "C310") (pin "1") (pinfunction "1_1") (pintype "passive"))
      (node (ref "C311") (pin "1") (pinfunction "1_1") (pintype "passive"))
      (node (ref "C313") (pin "1") (pinfunction "1_1") (pintype "passive"))
      (node (ref "C314") (pin "1") (pinfunction "1_1") (pintype "passive"))
      (node (ref "C315") (pin "1") (pinfunction "1_1") (pintype "passive"))
      (node (ref "C316") (pin "1") (pinfunction "1_1") (pintype "passive"))
      (node (ref "C317") (pin "1") (pinfunction "1_1") (pintype "passive"))
      (node (ref "C319") (pin "1") (pinfunction "1_1") (pintype "passive"))
      (node (ref "C320") (pin "1") (pinfunction "1_1") (pintype "passive"))
      (node (ref "C321") (pin "1") (pinfunction "1_1") (pintype "passive"))
      (node (ref "C322") (pin "1") (pinfunction "1_1") (pintype "passive"))
      (node (ref "C323") (pin "1") (pinfunction "1_1") (pintype "passive"))
      (node (ref "C324") (pin "1") (pinfunction "1_1") (pintype "passive"))
      (node (ref "C325") (pin "1") (pinfunction "1_1") (pintype "passive"))
      (node (ref "C326") (pin "1") (pinfunction "1_1") (pintype "passive"))
      (node (ref "C327") (pin "1") (pinfunction "1_1") (pintype "passive"))
      (node (ref "C329") (pin "1") (pinfunction "1_1") (pintype "passive"))
      (node (ref "C330") (pin "1") (pinfunction "1_1") (pintype "passive"))
      (node (ref "CN300") (pin "2") (pinfunction "GND_2") (pintype "power_in"))
      (node (ref "CN300") (pin "3") (pinfunction "GND_3") (pintype "power_in"))
      (node (ref "LED301") (pin "3") (pinfunction "BLUE_3") (pintype "passive"))
      (node (ref "Q300") (pin "2") (pinfunction "S_2") (pintype "passive"))
      (node (ref "R303") (pin "1") (pinfunction "1_1") (pintype "passive"))
      (node (ref "R304") (pin "1") (pinfunction "1_1") (pintype "passive"))
      (node (ref "R307") (pin "1") (pinfunction "1_1") (pintype "passive"))
      (node (ref "R311") (pin "1") (pinfunction "1_1") (pintype "passive"))
      (node (ref "R312") (pin "1") (pinfunction "1_1") (pintype "passive"))
      (node (ref "R317") (pin "1") (pinfunction "1_1") (pintype "passive"))
      (node (ref "R318") (pin "1") (pinfunction "1_1") (pintype "passive"))
      (node (ref "R320") (pin "1") (pinfunction "1_1") (pintype "passive"))
      (node (ref "R326") (pin "1") (pinfunction "1_1") (pintype "passive"))
      (node (ref "R327") (pin "1") (pinfunction "1_1") (pintype "passive"))
      (node (ref "SB301") (pin "2") (pinfunction "2_2") (pintype "passive"))
      (node (ref "U300") (pin "4") (pinfunction "PGND_4") (pintype "power_in"))
      (node (ref "U300") (pin "8") (pinfunction "SGND_8") (pintype "power_in"))
      (node (ref "U300") (pin "9") (pinfunction "PGND_9") (pintype "power_in"))
      (node (ref "U301") (pin "11") (pinfunction "GND_11") (pintype "power_in"))
      (node (ref "U302") (pin "4") (pinfunction "PGND_4") (pintype "power_in"))
      (node (ref "U302") (pin "8") (pinfunction "SGND_8") (pintype "power_in"))
      (node (ref "U302") (pin "9") (pinfunction "PGND_9") (pintype "power_in"))
      (node (ref "U303") (pin "4") (pinfunction "PGND_4") (pintype "power_in"))
      (node (ref "U303") (pin "8") (pinfunction "SGND_8") (pintype "power_in"))
      (node (ref "U303") (pin "9") (pinfunction "PGND_9") (pintype "power_in"))
      (node (ref "U304") (pin "1") (pinfunction "GND_1") (pintype "passive"))
      (node (ref "U305") (pin "4") (pinfunction "PGND_4") (pintype "power_in"))
      (node (ref "U305") (pin "8") (pinfunction "SGND_8") (pintype "power_in"))
      (node (ref "U305") (pin "9") (pinfunction "PGND_9") (pintype "power_in"))
    )
    (net (code "35") (name "Net-(LED301-Common_Anode)") (class "Default")
      (node (ref "LED301") (pin "4") (pinfunction "Common_Anode_4") (pintype "passive"))
      (node (ref "R328") (pin "1") (pinfunction "1_1") (pintype "passive"))
    )
    (net (code "36") (name "Net-(Q300-G)") (class "Default")
      (node (ref "Q300") (pin "1") (pinfunction "G_1") (pintype "passive"))
      (node (ref "R325") (pin "1") (pinfunction "1_1") (pintype "passive"))
    )
    (net (code "37") (name "unconnected-(H300-Pad1)") (class "Default")
      (node (ref "H300") (pin "1") (pinfunction "1_1") (pintype "passive+no_connect"))
    )
    (net (code "38") (name "unconnected-(H301-Pad1)") (class "Default")
      (node (ref "H301") (pin "1") (pinfunction "1_1") (pintype "passive+no_connect"))
    )
    (net (code "39") (name "unconnected-(H302-Pad1)") (class "Default")
      (node (ref "H302") (pin "1") (pinfunction "1_1") (pintype "passive+no_connect"))
    )
    (net (code "40") (name "unconnected-(H303-Pad1)") (class "Default")
      (node (ref "H303") (pin "1") (pinfunction "1_1") (pintype "passive+no_connect"))
    )
    (net (code "41") (name "unconnected-(U300-NC-Pad5)") (class "Default")
      (node (ref "U300") (pin "5") (pinfunction "NC_5") (pintype "passive+no_connect"))
    )
    (net (code "42") (name "unconnected-(U302-NC-Pad5)") (class "Default")
      (node (ref "U302") (pin "5") (pinfunction "NC_5") (pintype "passive+no_connect"))
    )
    (net (code "43") (name "unconnected-(U303-NC-Pad5)") (class "Default")
      (node (ref "U303") (pin "5") (pinfunction "NC_5") (pintype "passive+no_connect"))
    )
    (net (code "44") (name "unconnected-(U305-NC-Pad5)") (class "Default")
      (node (ref "U305") (pin "5") (pinfunction "NC_5") (pintype "passive+no_connect"))
    )
  )
)
